# Pure_LFO.net
KiCad netlist of a schematic drawn in EAGLE
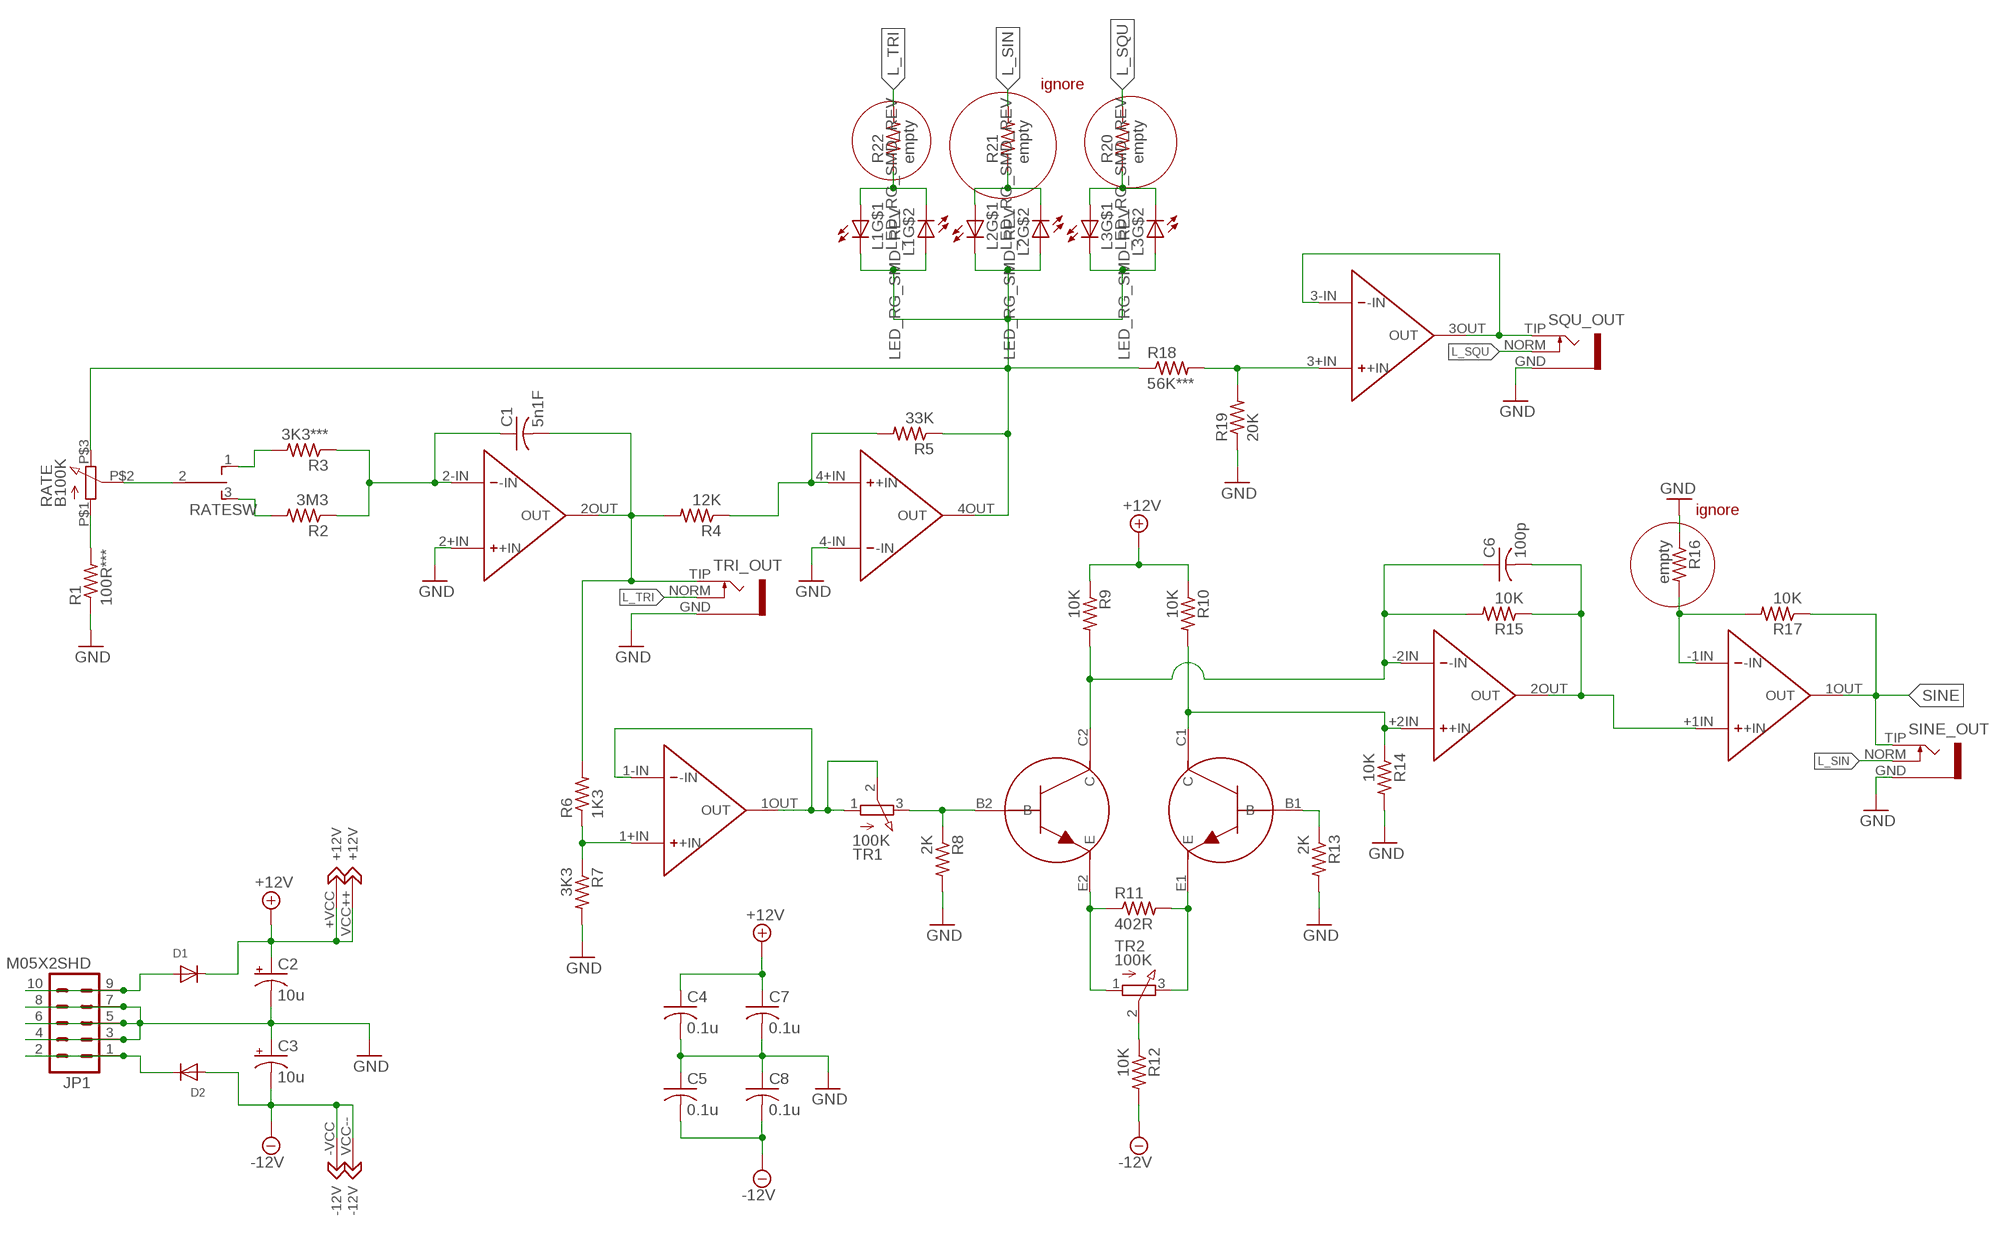
[diagram p0: schematic, sheet 1]

(export (version "E")
  (design (tool "Eeschema 10.0.6"))
  (components
    (comp (ref "C1")
      (value "5n1F")
      (footprint "eagle-import:C0805K")
      (libsource (lib "eagle-import") (part "C-USC0805K"))
    )
    (comp (ref "C2")
      (value "10u")
      (footprint "eagle-import:153CLV-0505")
      (libsource (lib "eagle-import") (part "CPOL-US153CLV-0505"))
    )
    (comp (ref "C3")
      (value "10u")
      (footprint "eagle-import:153CLV-0505")
      (libsource (lib "eagle-import") (part "CPOL-US153CLV-0505"))
    )
    (comp (ref "C4")
      (value "0.1u")
      (footprint "eagle-import:C0805K")
      (libsource (lib "eagle-import") (part "C-USC0805K"))
    )
    (comp (ref "C5")
      (value "0.1u")
      (footprint "eagle-import:C0805K")
      (libsource (lib "eagle-import") (part "C-USC0805K"))
    )
    (comp (ref "C6")
      (value "100p")
      (footprint "eagle-import:C0805K")
      (libsource (lib "eagle-import") (part "C-USC0805K"))
    )
    (comp (ref "C7")
      (value "0.1u")
      (footprint "eagle-import:C0805K")
      (libsource (lib "eagle-import") (part "C-USC0805K"))
    )
    (comp (ref "C8")
      (value "0.1u")
      (footprint "eagle-import:C0805K")
      (libsource (lib "eagle-import") (part "C-USC0805K"))
    )
    (comp (ref "D1")
      (value "DIODESMA")
      (footprint "eagle-import:SMADIODE")
      (libsource (lib "eagle-import") (part "DIODESMA"))
    )
    (comp (ref "D2")
      (value "DIODESMA")
      (footprint "eagle-import:SMADIODE")
      (libsource (lib "eagle-import") (part "DIODESMA"))
    )
    (comp (ref "JP1")
      (value "M05X2SHD")
      (footprint "eagle-import:2X5-SHROUDED")
      (libsource (lib "eagle-import") (part "M05X2SHD"))
    )
    (comp (ref "L1")
      (value "LED_RG_SMD_REV")
      (footprint "eagle-import:LSG_T77K")
      (libsource (lib "eagle-import") (part "LED_RG_SMD_REV"))
    )
    (comp (ref "L2")
      (value "LED_RG_SMD_REV")
      (footprint "eagle-import:LSG_T77K")
      (libsource (lib "eagle-import") (part "LED_RG_SMD_REV"))
    )
    (comp (ref "L3")
      (value "LED_RG_SMD_REV")
      (footprint "eagle-import:LSG_T77K")
      (libsource (lib "eagle-import") (part "LED_RG_SMD_REV"))
    )
    (comp (ref "R1")
      (value "100R***")
      (footprint "eagle-import:R0805")
      (libsource (lib "eagle-import") (part "R-US_R0805"))
    )
    (comp (ref "R2")
      (value "3M3")
      (footprint "eagle-import:R0805")
      (libsource (lib "eagle-import") (part "R-US_R0805"))
    )
    (comp (ref "R3")
      (value "3K3***")
      (footprint "eagle-import:R0805")
      (libsource (lib "eagle-import") (part "R-US_R0805"))
    )
    (comp (ref "R4")
      (value "12K")
      (footprint "eagle-import:R0805")
      (libsource (lib "eagle-import") (part "R-US_R0805"))
    )
    (comp (ref "R5")
      (value "33K")
      (footprint "eagle-import:R0805")
      (libsource (lib "eagle-import") (part "R-US_R0805"))
    )
    (comp (ref "R6")
      (value "1K3")
      (footprint "eagle-import:R0805")
      (libsource (lib "eagle-import") (part "R-US_R0805"))
    )
    (comp (ref "R7")
      (value "3K3")
      (footprint "eagle-import:R0805")
      (libsource (lib "eagle-import") (part "R-US_R0805"))
    )
    (comp (ref "R8")
      (value "2K")
      (footprint "eagle-import:R0805")
      (libsource (lib "eagle-import") (part "R-US_R0805"))
    )
    (comp (ref "R9")
      (value "10K")
      (footprint "eagle-import:R0805")
      (libsource (lib "eagle-import") (part "R-US_R0805"))
    )
    (comp (ref "R10")
      (value "10K")
      (footprint "eagle-import:R0805")
      (libsource (lib "eagle-import") (part "R-US_R0805"))
    )
    (comp (ref "R11")
      (value "402R")
      (footprint "eagle-import:R0805")
      (libsource (lib "eagle-import") (part "R-US_R0805"))
    )
    (comp (ref "R12")
      (value "10K")
      (footprint "eagle-import:R0805")
      (libsource (lib "eagle-import") (part "R-US_R0805"))
    )
    (comp (ref "R13")
      (value "2K")
      (footprint "eagle-import:R0805")
      (libsource (lib "eagle-import") (part "R-US_R0805"))
    )
    (comp (ref "R14")
      (value "10K")
      (footprint "eagle-import:R0805")
      (libsource (lib "eagle-import") (part "R-US_R0805"))
    )
    (comp (ref "R15")
      (value "10K")
      (footprint "eagle-import:R0805")
      (libsource (lib "eagle-import") (part "R-US_R0805"))
    )
    (comp (ref "R16")
      (value "empty")
      (footprint "eagle-import:R0805")
      (libsource (lib "eagle-import") (part "R-US_R0805"))
    )
    (comp (ref "R17")
      (value "10K")
      (footprint "eagle-import:R0805")
      (libsource (lib "eagle-import") (part "R-US_R0805"))
    )
    (comp (ref "R18")
      (value "56K***")
      (footprint "eagle-import:R0805")
      (libsource (lib "eagle-import") (part "R-US_R0805"))
    )
    (comp (ref "R19")
      (value "20K")
      (footprint "eagle-import:R0805")
      (libsource (lib "eagle-import") (part "R-US_R0805"))
    )
    (comp (ref "R20")
      (value "empty")
      (footprint "eagle-import:R0805")
      (libsource (lib "eagle-import") (part "R-US_R0805"))
    )
    (comp (ref "R21")
      (value "empty")
      (footprint "eagle-import:R0805")
      (libsource (lib "eagle-import") (part "R-US_R0805"))
    )
    (comp (ref "R22")
      (value "empty")
      (footprint "eagle-import:R0805")
      (libsource (lib "eagle-import") (part "R-US_R0805"))
    )
    (comp (ref "RATE")
      (value "B100K")
      (footprint "eagle-import:Q-POT")
      (libsource (lib "eagle-import") (part "Q-POT"))
    )
    (comp (ref "RATESW")
      (value "TOGGLE_ON_OFF_ON")
      (footprint "eagle-import:TOGGLE_ON_OFF_ON")
      (libsource (lib "eagle-import") (part "TOGGLE_ON_OFF_ON"))
    )
    (comp (ref "SINE_OUT")
      (value "S_JACK")
      (footprint "eagle-import:S_JACK")
      (libsource (lib "eagle-import") (part "S_JACK"))
    )
    (comp (ref "SQU_OUT")
      (value "S_JACK")
      (footprint "eagle-import:S_JACK")
      (libsource (lib "eagle-import") (part "S_JACK"))
    )
    (comp (ref "T3")
      (value "TRANS_PAIR")
      (footprint "eagle-import:TRANS_PAIR")
      (libsource (lib "eagle-import") (part "TRANS_PAIR"))
    )
    (comp (ref "TR1")
      (value "100K")
      (footprint "eagle-import:TRIM_3269W")
      (libsource (lib "eagle-import") (part "TRIM_3269W"))
    )
    (comp (ref "TR2")
      (value "100K")
      (footprint "eagle-import:TRIM_3269W")
      (libsource (lib "eagle-import") (part "TRIM_3269W"))
    )
    (comp (ref "TRI_OUT")
      (value "S_JACK")
      (footprint "eagle-import:S_JACK")
      (libsource (lib "eagle-import") (part "S_JACK"))
    )
    (comp (ref "U1")
      (value "DUAL_OPAMP")
      (footprint "eagle-import:DUAL_OPAMP")
      (libsource (lib "eagle-import") (part "DUAL_OPAMP"))
    )
    (comp (ref "U2")
      (value "QUAD_OPAMP")
      (footprint "eagle-import:QUAD_OPAMP")
      (libsource (lib "eagle-import") (part "QUAD_OPAMP"))
    )
  )
  (nets
    (net (code "1") (name "+12V") (class "Default")
      (node (ref "C2") (pin "+") (pinfunction "+_+") (pintype "passive"))
      (node (ref "C4") (pin "1") (pinfunction "1_1") (pintype "passive"))
      (node (ref "C7") (pin "1") (pinfunction "1_1") (pintype "passive"))
      (node (ref "D1") (pin "C") (pinfunction "C_C") (pintype "passive"))
      (node (ref "R10") (pin "1") (pinfunction "1_1") (pintype "passive"))
      (node (ref "R9") (pin "1") (pinfunction "1_1") (pintype "passive"))
      (node (ref "U1") (pin "+VCC") (pinfunction "+12V_+VCC") (pintype "bidirectional"))
      (node (ref "U2") (pin "VCC++") (pinfunction "+12V_VCC++") (pintype "bidirectional"))
    )
    (net (code "2") (name "-12V") (class "Default")
      (node (ref "C3") (pin "-") (pinfunction "-_-") (pintype "passive"))
      (node (ref "C5") (pin "2") (pinfunction "2_2") (pintype "passive"))
      (node (ref "C8") (pin "2") (pinfunction "2_2") (pintype "passive"))
      (node (ref "D2") (pin "A") (pinfunction "A_A") (pintype "passive"))
      (node (ref "R12") (pin "2") (pinfunction "2_2") (pintype "passive"))
      (node (ref "U1") (pin "-VCC") (pinfunction "-12V_-VCC") (pintype "bidirectional"))
      (node (ref "U2") (pin "VCC--") (pinfunction "-12V_VCC--") (pintype "bidirectional"))
    )
    (net (code "3") (name "GND") (class "Default")
      (node (ref "C2") (pin "-") (pinfunction "-_-") (pintype "passive"))
      (node (ref "C3") (pin "+") (pinfunction "+_+") (pintype "passive"))
      (node (ref "C4") (pin "2") (pinfunction "2_2") (pintype "passive"))
      (node (ref "C5") (pin "1") (pinfunction "1_1") (pintype "passive"))
      (node (ref "C7") (pin "2") (pinfunction "2_2") (pintype "passive"))
      (node (ref "C8") (pin "1") (pinfunction "1_1") (pintype "passive"))
      (node (ref "JP1") (pin "3") (pinfunction "3_3") (pintype "passive"))
      (node (ref "JP1") (pin "4") (pinfunction "4_4") (pintype "passive"))
      (node (ref "JP1") (pin "5") (pinfunction "5_5") (pintype "passive"))
      (node (ref "JP1") (pin "6") (pinfunction "6_6") (pintype "passive"))
      (node (ref "JP1") (pin "7") (pinfunction "7_7") (pintype "passive"))
      (node (ref "JP1") (pin "8") (pinfunction "8_8") (pintype "passive"))
      (node (ref "R1") (pin "1") (pinfunction "1_1") (pintype "passive"))
      (node (ref "R13") (pin "2") (pinfunction "2_2") (pintype "passive"))
      (node (ref "R14") (pin "2") (pinfunction "2_2") (pintype "passive"))
      (node (ref "R16") (pin "1") (pinfunction "1_1") (pintype "passive"))
      (node (ref "R19") (pin "1") (pinfunction "1_1") (pintype "passive"))
      (node (ref "R7") (pin "2") (pinfunction "2_2") (pintype "passive"))
      (node (ref "R8") (pin "2") (pinfunction "2_2") (pintype "passive"))
      (node (ref "SINE_OUT") (pin "GND") (pinfunction "GND_GND") (pintype "passive"))
      (node (ref "SQU_OUT") (pin "GND") (pinfunction "GND_GND") (pintype "passive"))
      (node (ref "TRI_OUT") (pin "GND") (pinfunction "GND_GND") (pintype "passive"))
      (node (ref "U2") (pin "2+IN") (pinfunction "+IN_2+IN") (pintype "bidirectional"))
      (node (ref "U2") (pin "4-IN") (pinfunction "-IN_4-IN") (pintype "bidirectional"))
    )
    (net (code "4") (name "L_SIN") (class "Default")
      (node (ref "R21") (pin "2") (pinfunction "2_2") (pintype "passive"))
      (node (ref "SINE_OUT") (pin "NORM") (pinfunction "NORM_NORM") (pintype "passive"))
    )
    (net (code "5") (name "L_SQU") (class "Default")
      (node (ref "R20") (pin "2") (pinfunction "2_2") (pintype "passive"))
      (node (ref "SQU_OUT") (pin "NORM") (pinfunction "NORM_NORM") (pintype "passive"))
    )
    (net (code "6") (name "L_TRI") (class "Default")
      (node (ref "R22") (pin "2") (pinfunction "2_2") (pintype "passive"))
      (node (ref "TRI_OUT") (pin "NORM") (pinfunction "NORM_NORM") (pintype "passive"))
    )
    (net (code "7") (name "Net-(D1-PadA)") (class "Default")
      (node (ref "D1") (pin "A") (pinfunction "A_A") (pintype "passive"))
      (node (ref "JP1") (pin "10") (pinfunction "10_10") (pintype "passive"))
      (node (ref "JP1") (pin "9") (pinfunction "9_9") (pintype "passive"))
    )
    (net (code "8") (name "Net-(D2-PadC)") (class "Default")
      (node (ref "D2") (pin "C") (pinfunction "C_C") (pintype "passive"))
      (node (ref "JP1") (pin "1") (pinfunction "1_1") (pintype "passive"))
      (node (ref "JP1") (pin "2") (pinfunction "2_2") (pintype "passive"))
    )
    (net (code "9") (name "Net-(L1A-A)") (class "Default")
      (node (ref "L1") (pin "2") (pinfunction "A_2") (pintype "passive"))
      (node (ref "L1") (pin "3") (pinfunction "C_3") (pintype "passive"))
      (node (ref "R22") (pin "1") (pinfunction "1_1") (pintype "passive"))
    )
    (net (code "10") (name "Net-(L1A-C)") (class "Default")
      (node (ref "L1") (pin "1") (pinfunction "C_1") (pintype "passive"))
      (node (ref "L1") (pin "4") (pinfunction "A_4") (pintype "passive"))
      (node (ref "L2") (pin "1") (pinfunction "C_1") (pintype "passive"))
      (node (ref "L2") (pin "4") (pinfunction "A_4") (pintype "passive"))
      (node (ref "L3") (pin "1") (pinfunction "C_1") (pintype "passive"))
      (node (ref "L3") (pin "4") (pinfunction "A_4") (pintype "passive"))
      (node (ref "R18") (pin "1") (pinfunction "1_1") (pintype "passive"))
      (node (ref "R5") (pin "1") (pinfunction "1_1") (pintype "passive"))
      (node (ref "RATE") (pin "P$3") (pinfunction "3_P$3") (pintype "passive"))
      (node (ref "U2") (pin "4OUT") (pinfunction "OUT_4OUT") (pintype "bidirectional"))
    )
    (net (code "11") (name "Net-(L2A-A)") (class "Default")
      (node (ref "L2") (pin "2") (pinfunction "A_2") (pintype "passive"))
      (node (ref "L2") (pin "3") (pinfunction "C_3") (pintype "passive"))
      (node (ref "R21") (pin "1") (pinfunction "1_1") (pintype "passive"))
    )
    (net (code "12") (name "Net-(L3A-A)") (class "Default")
      (node (ref "L3") (pin "2") (pinfunction "A_2") (pintype "passive"))
      (node (ref "L3") (pin "3") (pinfunction "C_3") (pintype "passive"))
      (node (ref "R20") (pin "1") (pinfunction "1_1") (pintype "passive"))
    )
    (net (code "13") (name "Net-(R12-Pad1)") (class "Default")
      (node (ref "R12") (pin "1") (pinfunction "1_1") (pintype "passive"))
      (node (ref "TR2") (pin "2") (pinfunction "2_2") (pintype "passive"))
    )
    (net (code "14") (name "Net-(RATE-1)") (class "Default")
      (node (ref "R1") (pin "2") (pinfunction "2_2") (pintype "passive"))
      (node (ref "RATE") (pin "P$1") (pinfunction "1_P$1") (pintype "passive"))
    )
    (net (code "15") (name "Net-(RATE-2)") (class "Default")
      (node (ref "RATE") (pin "P$2") (pinfunction "2_P$2") (pintype "passive"))
      (node (ref "RATESW") (pin "2") (pinfunction "P_2") (pintype "passive"))
    )
    (net (code "16") (name "Net-(RATESW-O)") (class "Default")
      (node (ref "R3") (pin "2") (pinfunction "2_2") (pintype "passive"))
      (node (ref "RATESW") (pin "1") (pinfunction "O_1") (pintype "passive"))
    )
    (net (code "17") (name "Net-(RATESW-S)") (class "Default")
      (node (ref "R2") (pin "2") (pinfunction "2_2") (pintype "passive"))
      (node (ref "RATESW") (pin "3") (pinfunction "S_3") (pintype "passive"))
    )
    (net (code "18") (name "Net-(T3A-B)") (class "Default")
      (node (ref "R13") (pin "1") (pinfunction "1_1") (pintype "passive"))
      (node (ref "T3") (pin "B1") (pinfunction "B_B1") (pintype "bidirectional"))
    )
    (net (code "19") (name "Net-(T3A-C)") (class "Default")
      (node (ref "R10") (pin "2") (pinfunction "2_2") (pintype "passive"))
      (node (ref "R14") (pin "1") (pinfunction "1_1") (pintype "passive"))
      (node (ref "T3") (pin "C1") (pinfunction "C_C1") (pintype "bidirectional"))
      (node (ref "U1") (pin "+2IN") (pinfunction "+IN_+2IN") (pintype "bidirectional"))
    )
    (net (code "20") (name "Net-(T3A-E)") (class "Default")
      (node (ref "R11") (pin "2") (pinfunction "2_2") (pintype "passive"))
      (node (ref "T3") (pin "E1") (pinfunction "E_E1") (pintype "bidirectional"))
      (node (ref "TR2") (pin "3") (pinfunction "3_3") (pintype "passive"))
    )
    (net (code "21") (name "Net-(T3B-B)") (class "Default")
      (node (ref "R8") (pin "1") (pinfunction "1_1") (pintype "passive"))
      (node (ref "T3") (pin "B2") (pinfunction "B_B2") (pintype "bidirectional"))
      (node (ref "TR1") (pin "3") (pinfunction "3_3") (pintype "passive"))
    )
    (net (code "22") (name "Net-(T3B-C)") (class "Default")
      (node (ref "C6") (pin "1") (pinfunction "1_1") (pintype "passive"))
      (node (ref "R15") (pin "2") (pinfunction "2_2") (pintype "passive"))
      (node (ref "R9") (pin "2") (pinfunction "2_2") (pintype "passive"))
      (node (ref "T3") (pin "C2") (pinfunction "C_C2") (pintype "bidirectional"))
      (node (ref "U1") (pin "-2IN") (pinfunction "-IN_-2IN") (pintype "bidirectional"))
    )
    (net (code "23") (name "Net-(T3B-E)") (class "Default")
      (node (ref "R11") (pin "1") (pinfunction "1_1") (pintype "passive"))
      (node (ref "T3") (pin "E2") (pinfunction "E_E2") (pintype "bidirectional"))
      (node (ref "TR2") (pin "1") (pinfunction "1_1") (pintype "passive"))
    )
    (net (code "24") (name "Net-(U1A-+IN)") (class "Default")
      (node (ref "C6") (pin "2") (pinfunction "2_2") (pintype "passive"))
      (node (ref "R15") (pin "1") (pinfunction "1_1") (pintype "passive"))
      (node (ref "U1") (pin "+1IN") (pinfunction "+IN_+1IN") (pintype "bidirectional"))
      (node (ref "U1") (pin "2OUT") (pinfunction "OUT_2OUT") (pintype "bidirectional"))
    )
    (net (code "25") (name "Net-(U1A--IN)") (class "Default")
      (node (ref "R16") (pin "2") (pinfunction "2_2") (pintype "passive"))
      (node (ref "R17") (pin "2") (pinfunction "2_2") (pintype "passive"))
      (node (ref "U1") (pin "-1IN") (pinfunction "-IN_-1IN") (pintype "bidirectional"))
    )
    (net (code "26") (name "Net-(U2A-+IN)") (class "Default")
      (node (ref "R6") (pin "1") (pinfunction "1_1") (pintype "passive"))
      (node (ref "R7") (pin "1") (pinfunction "1_1") (pintype "passive"))
      (node (ref "U2") (pin "1+IN") (pinfunction "+IN_1+IN") (pintype "bidirectional"))
    )
    (net (code "27") (name "Net-(U2A--IN)") (class "Default")
      (node (ref "TR1") (pin "1") (pinfunction "1_1") (pintype "passive"))
      (node (ref "TR1") (pin "2") (pinfunction "2_2") (pintype "passive"))
      (node (ref "U2") (pin "1-IN") (pinfunction "-IN_1-IN") (pintype "bidirectional"))
      (node (ref "U2") (pin "1OUT") (pinfunction "OUT_1OUT") (pintype "bidirectional"))
    )
    (net (code "28") (name "Net-(U2B--IN)") (class "Default")
      (node (ref "C1") (pin "1") (pinfunction "1_1") (pintype "passive"))
      (node (ref "R2") (pin "1") (pinfunction "1_1") (pintype "passive"))
      (node (ref "R3") (pin "1") (pinfunction "1_1") (pintype "passive"))
      (node (ref "U2") (pin "2-IN") (pinfunction "-IN_2-IN") (pintype "bidirectional"))
    )
    (net (code "29") (name "Net-(U2B-OUT)") (class "Default")
      (node (ref "C1") (pin "2") (pinfunction "2_2") (pintype "passive"))
      (node (ref "R4") (pin "2") (pinfunction "2_2") (pintype "passive"))
      (node (ref "R6") (pin "2") (pinfunction "2_2") (pintype "passive"))
      (node (ref "TRI_OUT") (pin "TIP") (pinfunction "TIP_TIP") (pintype "passive"))
      (node (ref "U2") (pin "2OUT") (pinfunction "OUT_2OUT") (pintype "bidirectional"))
    )
    (net (code "30") (name "Net-(U2C-+IN)") (class "Default")
      (node (ref "R18") (pin "2") (pinfunction "2_2") (pintype "passive"))
      (node (ref "R19") (pin "2") (pinfunction "2_2") (pintype "passive"))
      (node (ref "U2") (pin "3+IN") (pinfunction "+IN_3+IN") (pintype "bidirectional"))
    )
    (net (code "31") (name "Net-(U2C--IN)") (class "Default")
      (node (ref "SQU_OUT") (pin "TIP") (pinfunction "TIP_TIP") (pintype "passive"))
      (node (ref "U2") (pin "3-IN") (pinfunction "-IN_3-IN") (pintype "bidirectional"))
      (node (ref "U2") (pin "3OUT") (pinfunction "OUT_3OUT") (pintype "bidirectional"))
    )
    (net (code "32") (name "Net-(U2D-+IN)") (class "Default")
      (node (ref "R4") (pin "1") (pinfunction "1_1") (pintype "passive"))
      (node (ref "R5") (pin "2") (pinfunction "2_2") (pintype "passive"))
      (node (ref "U2") (pin "4+IN") (pinfunction "+IN_4+IN") (pintype "bidirectional"))
    )
    (net (code "33") (name "SINE") (class "Default")
      (node (ref "R17") (pin "1") (pinfunction "1_1") (pintype "passive"))
      (node (ref "SINE_OUT") (pin "TIP") (pinfunction "TIP_TIP") (pintype "passive"))
      (node (ref "U1") (pin "1OUT") (pinfunction "OUT_1OUT") (pintype "bidirectional"))
    )
  )
)
